# BUZZ.net
KiCad netlist of a schematic drawn in Altium Designer
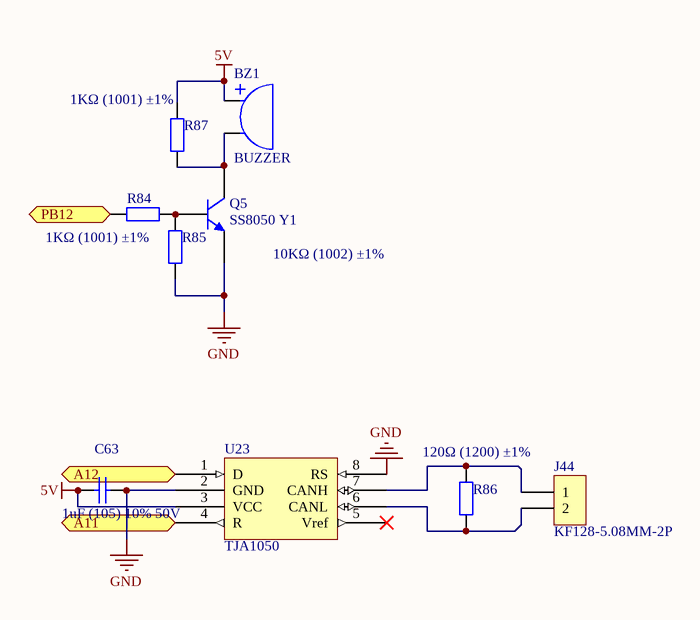
[diagram p0: BUZZ.SchDoc]

(export (version "E")
  (design (tool "Eeschema 10.0.6"))
  (components
    (comp (ref "BZ1")
      (value "BUZZER")
      (footprint "BUZZER-D12.0X8.5-6.5-0.8")
      (description "Buzzer")
      (libsource (lib "淘宝封装") (part "BUZZER"))
    )
    (comp (ref "C63")
      (value "1uF (105) 10% 50V")
      (footprint "0805_C")
      (description "贴片电容")
      (libsource (lib "Cap") (part "0805 1uF (105) 10% 50V"))
    )
    (comp (ref "J44")
      (value "KF128-5.08MM-2P")
      (footprint "Connector:WJ2EDGR-5.08-2")
      (description "接线端子")
      (libsource (lib "Connector") (part "KF128-5.08MM-2P"))
    )
    (comp (ref "Q5")
      (value "SS8050 Y1")
      (footprint "SOT-23(SOT-23-3)")
      (description "三极管")
      (libsource (lib "Transistor_NPN") (part "SOT-23 SS8050 Y1"))
    )
    (comp (ref "R84")
      (value "1KΩ (1001) ±1%")
      (footprint "0805_R")
      (description "贴片电阻")
      (libsource (lib "") (part "0805 1KΩ (1001) 1%_1"))
    )
    (comp (ref "R85")
      (value "10KΩ (1002) ±1%")
      (footprint "0805_R")
      (description "贴片电阻")
      (libsource (lib "RES") (part "0805 10KΩ (1002) 1%"))
    )
    (comp (ref "R86")
      (value "120Ω (1200) ±1%")
      (footprint "0805_R")
      (description "贴片电阻")
      (libsource (lib "RES") (part "0805 120Ω (1200) 1%"))
    )
    (comp (ref "R87")
      (value "1KΩ (1001) ±1%")
      (footprint "0805_R")
      (description "贴片电阻")
      (libsource (lib "RES") (part "0805 1KΩ (1001) 1%"))
    )
    (comp (ref "U23") (value "TJA1050") (footprint "SOP-8") (libsource (lib "EXPLORER") (part "SN65HVD230D")))
  )
  (nets
    (net (code "1") (name "/A11") (class "Default")
      (node (ref "U23") (pin "4") (pinfunction "R_4") (pintype "output"))
    )
    (net (code "2") (name "/A12") (class "Default")
      (node (ref "U23") (pin "1") (pinfunction "D_1") (pintype "input"))
    )
    (net (code "3") (name "/PB12") (class "Default")
      (node (ref "R84") (pin "1") (pinfunction "1_1") (pintype "passive"))
    )
    (net (code "4") (name "5V") (class "Default")
      (node (ref "BZ1") (pin "1") (pinfunction "1_1") (pintype "passive"))
      (node (ref "C63") (pin "1") (pinfunction "1_1") (pintype "passive"))
      (node (ref "R87") (pin "2") (pinfunction "2_2") (pintype "passive"))
      (node (ref "U23") (pin "3") (pinfunction "VCC_3") (pintype "power_in"))
    )
    (net (code "5") (name "GND") (class "Default")
      (node (ref "C63") (pin "2") (pinfunction "2_2") (pintype "passive"))
      (node (ref "Q5") (pin "2") (pinfunction "E_2") (pintype "passive"))
      (node (ref "R85") (pin "1") (pinfunction "1_1") (pintype "passive"))
      (node (ref "U23") (pin "2") (pinfunction "GND_2") (pintype "power_in"))
      (node (ref "U23") (pin "8") (pinfunction "RS_8") (pintype "input"))
    )
    (net (code "6") (name "Net-(Q5-B)") (class "Default")
      (node (ref "Q5") (pin "1") (pinfunction "B_1") (pintype "passive"))
      (node (ref "R84") (pin "2") (pinfunction "2_2") (pintype "passive"))
      (node (ref "R85") (pin "2") (pinfunction "2_2") (pintype "passive"))
    )
    (net (code "7") (name "Net-(Q5-C)") (class "Default")
      (node (ref "BZ1") (pin "2") (pinfunction "2_2") (pintype "passive"))
      (node (ref "Q5") (pin "3") (pinfunction "C_3") (pintype "passive"))
      (node (ref "R87") (pin "1") (pinfunction "1_1") (pintype "passive"))
    )
    (net (code "8") (name "Net-(U23-CANH)") (class "Default")
      (node (ref "J44") (pin "1") (pinfunction "1_1") (pintype "passive"))
      (node (ref "R86") (pin "2") (pinfunction "2_2") (pintype "passive"))
      (node (ref "U23") (pin "7") (pinfunction "CANH_7") (pintype "bidirectional"))
    )
    (net (code "9") (name "Net-(U23-CANL)") (class "Default")
      (node (ref "J44") (pin "2") (pinfunction "2_2") (pintype "passive"))
      (node (ref "R86") (pin "1") (pinfunction "1_1") (pintype "passive"))
      (node (ref "U23") (pin "6") (pinfunction "CANL_6") (pintype "bidirectional"))
    )
    (net (code "10") (name "unconnected-(U23-Vref-Pad5)") (class "Default")
      (node (ref "U23") (pin "5") (pinfunction "Vref_5") (pintype "output+no_connect"))
    )
  )
)
